# -_V2.net
KiCad netlist of a schematic drawn in EasyEDA Pro
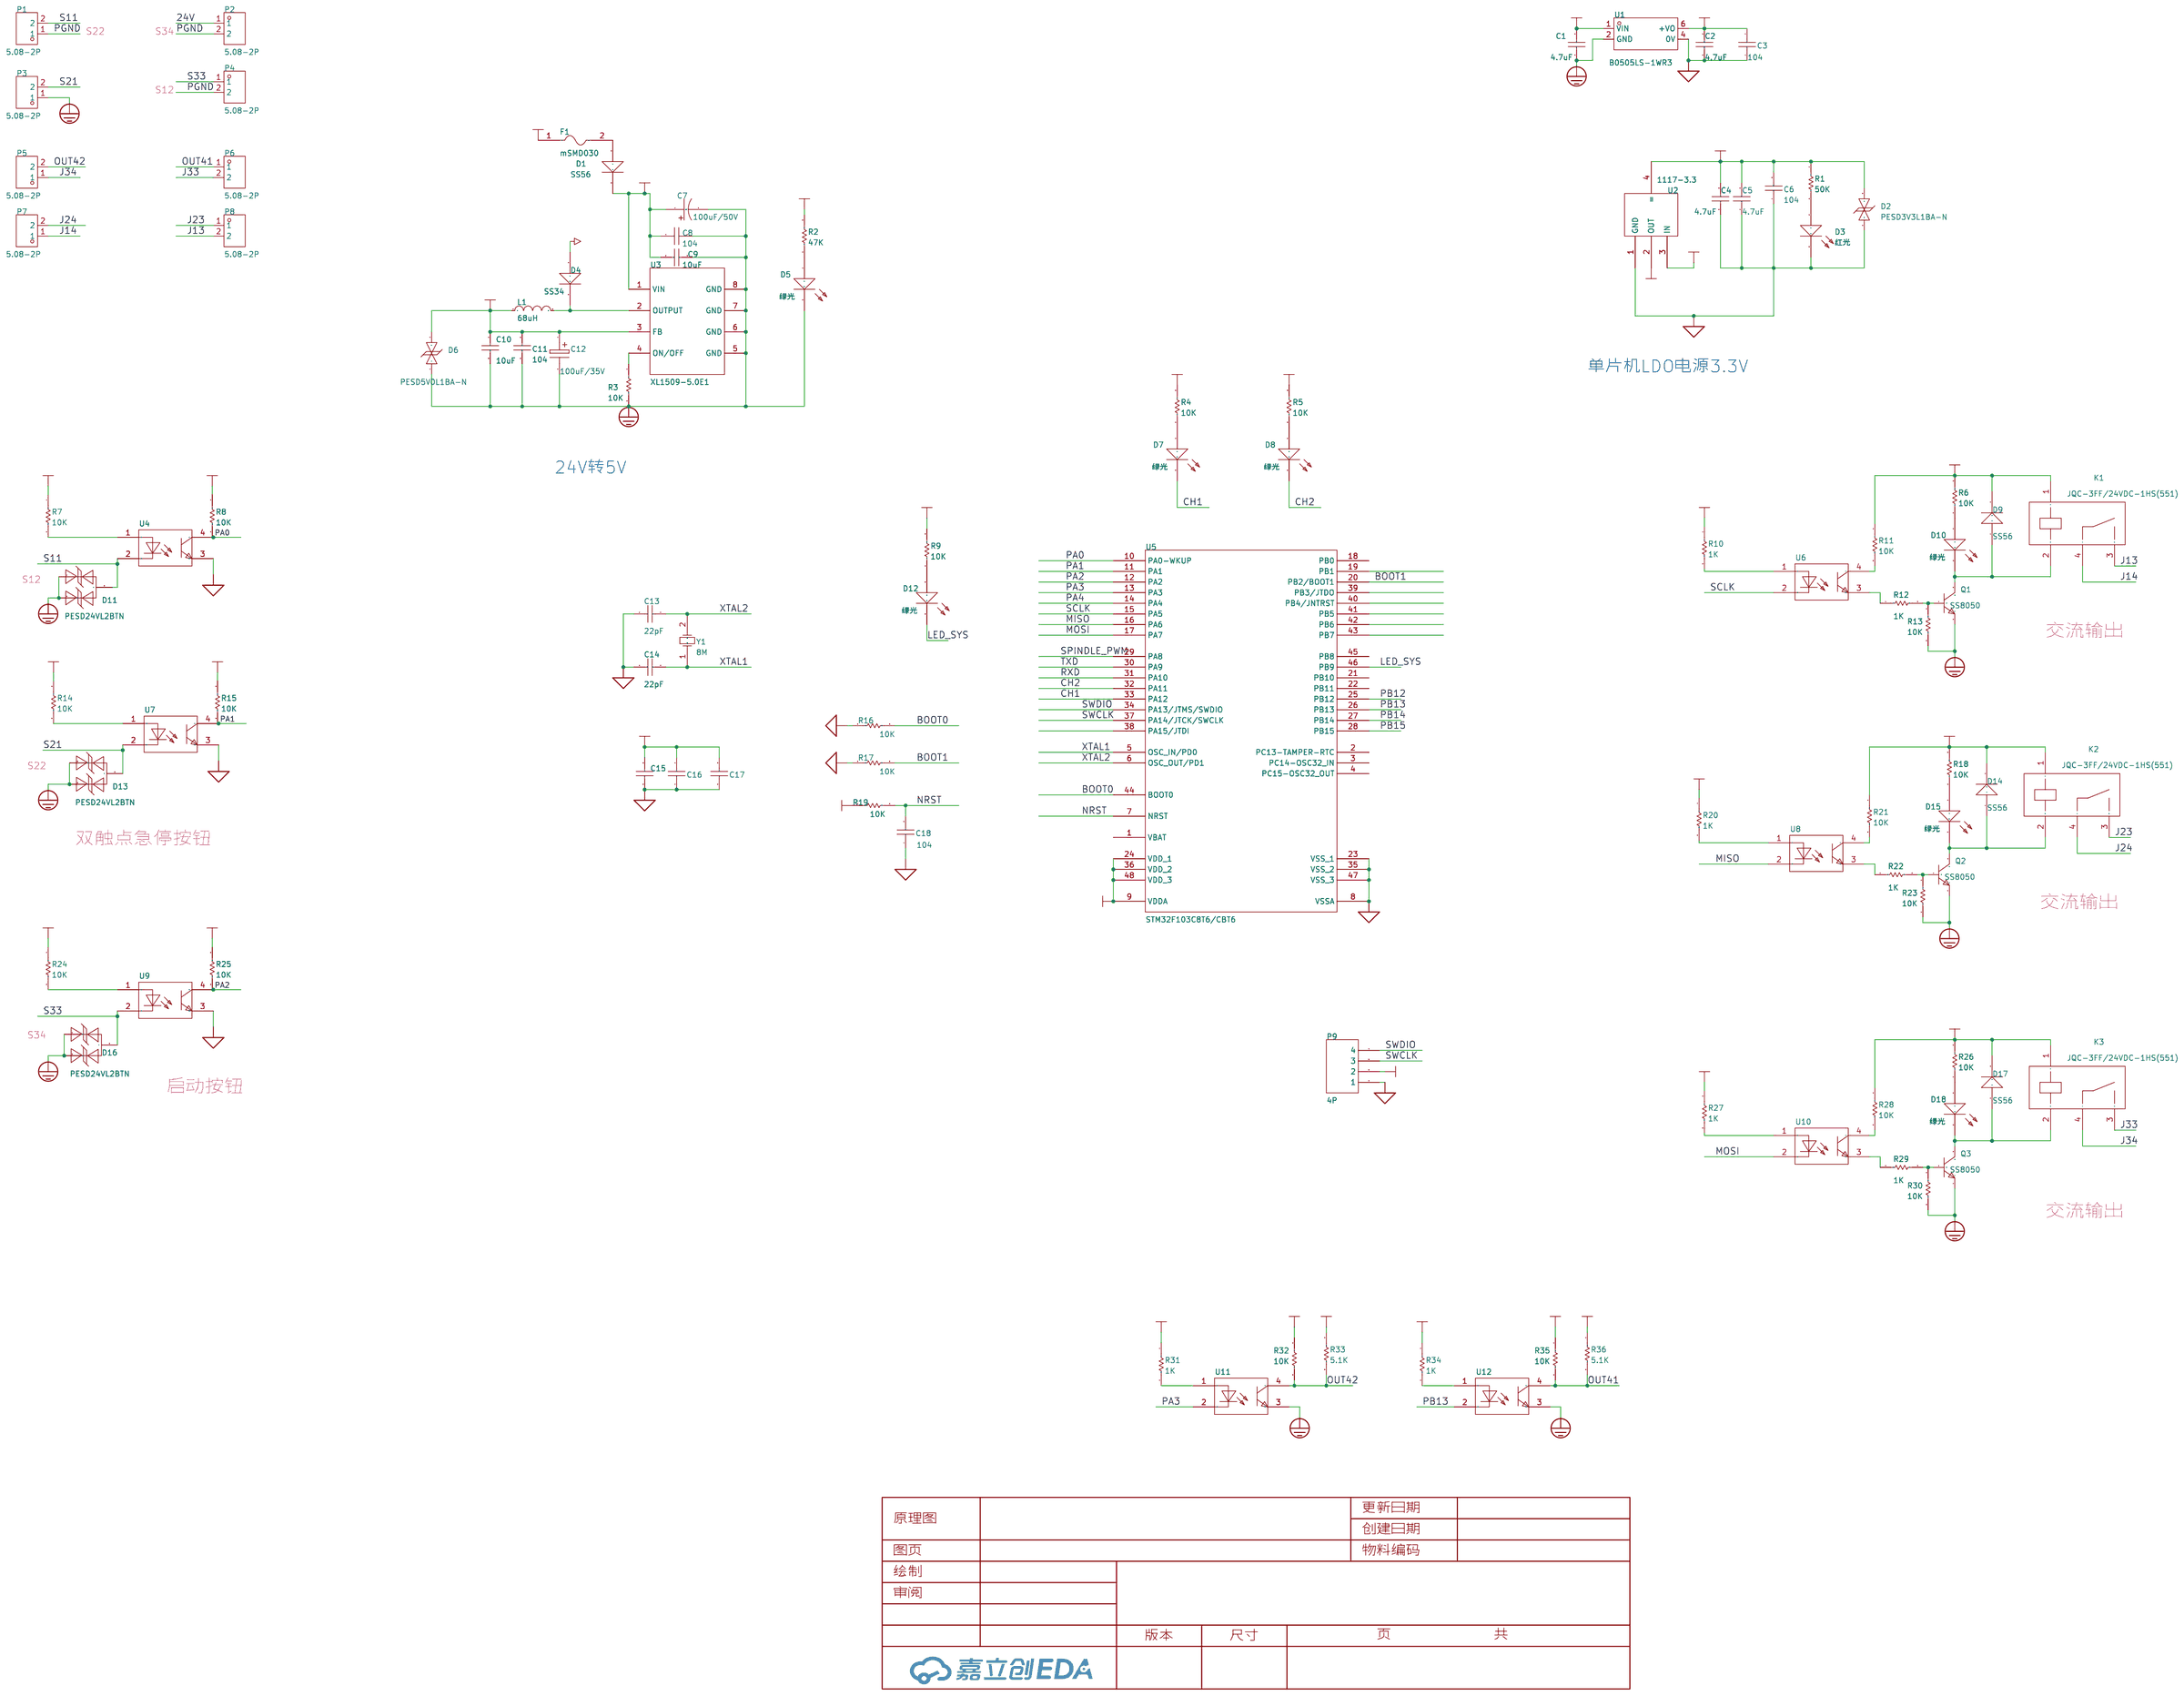
[diagram p0: schematic sheet]

(export (version "E")
  (design (tool "Eeschema 10.0.6"))
  (components
    (comp (ref "C1") (value "4.7uF") (libsource (lib "easyedapro") (part "CAP")))
    (comp (ref "C2") (value "4.7uF") (libsource (lib "easyedapro") (part "CAP")))
    (comp (ref "C3") (value "104") (libsource (lib "easyedapro") (part "CAP")))
    (comp (ref "C4") (value "4.7uF") (libsource (lib "easyedapro") (part "CAP")))
    (comp (ref "C5") (value "4.7uF") (libsource (lib "easyedapro") (part "CAP")))
    (comp (ref "C6")
      (value "104")
      (footprint "easyedapro:0603C")
      (description "Capacitor (Semiconductor SIM Model)")
      (libsource (lib "easyedapro") (part "Cap Semi"))
    )
    (comp (ref "C7")
      (value "100uF/50V")
      (footprint "easyedapro:CAP-SMD_BD10.0-L10.3-W10.3-LS11.0-R-RD")
      (fields (field (name "Manufacturer Part") "VZH101M1HTR-1008") (field (name "Manufacturer") "lelon(立隆)"))
      (libsource (lib "easyedapro") (part "VZH101M1HTR-1008"))
    )
    (comp (ref "C8")
      (value "104")
      (footprint "easyedapro:0603C")
      (description "Capacitor (Semiconductor SIM Model)")
      (libsource (lib "easyedapro") (part "Cap Semi"))
    )
    (comp (ref "C9") (value "10uF") (libsource (lib "easyedapro") (part "CAP")))
    (comp (ref "C10") (value "10uF") (libsource (lib "easyedapro") (part "CAP")))
    (comp (ref "C11")
      (value "104")
      (footprint "easyedapro:0603C")
      (description "Capacitor (Semiconductor SIM Model)")
      (libsource (lib "easyedapro") (part "Cap Semi"))
    )
    (comp (ref "C12")
      (value "100uF/35V")
      (footprint "easyedapro:0603C")
      (libsource (lib "easyedapro") (part "ELECTRO1"))
    )
    (comp (ref "C13")
      (value "100pF")
      (footprint "easyedapro:0603C")
      (description "Capacitor (Semiconductor SIM Model)")
      (libsource (lib "easyedapro") (part "Cap Semi"))
    )
    (comp (ref "C14")
      (value "100pF")
      (footprint "easyedapro:0603C")
      (description "Capacitor (Semiconductor SIM Model)")
      (libsource (lib "easyedapro") (part "Cap Semi"))
    )
    (comp (ref "C15") (value "104") (footprint "easyedapro:电解电容贴片6X6") (libsource (lib "") (part "CAP_1")))
    (comp (ref "C16") (value "104") (footprint "easyedapro:电解电容贴片6X6") (libsource (lib "") (part "CAP_1")))
    (comp (ref "C17") (value "104") (footprint "easyedapro:电解电容贴片6X6") (libsource (lib "") (part "CAP_1")))
    (comp (ref "C18")
      (value "104")
      (footprint "easyedapro:0603C")
      (description "Capacitor (Semiconductor SIM Model)")
      (libsource (lib "easyedapro") (part "Cap Semi"))
    )
    (comp (ref "D1") (value "SS56") (footprint "easyedapro:SMA") (libsource (lib "") (part "1N4148_1")))
    (comp (ref "D2")
      (value "PESD3V3L1BA-N")
      (footprint "easyedapro:SOD-523_L1.2-W0.8-LS1.6-BI")
      (description "极性:Bidirectional;反向关断电压（典型值）:5V (Max);击穿电压（最小值）:6V;箝位电压:15V;峰值脉冲电流（10/1000us）:5A (8/20us);")
      (fields (field (name "Manufacturer") "BORN伯恩半导体"))
      (libsource (lib "easyedapro") (part "PESD5V0S1BBN"))
    )
    (comp (ref "D3")
      (value "红光")
      (footprint "easyedapro:0603LED")
      (libsource (lib "easyedapro") (part "LED"))
    )
    (comp (ref "D4") (value "SS34") (libsource (lib "easyedapro") (part "1N4148")))
    (comp (ref "D5")
      (value "绿光")
      (footprint "easyedapro:0603LED")
      (libsource (lib "easyedapro") (part "LED"))
    )
    (comp (ref "D6")
      (value "PESD5V0L1BA-N")
      (footprint "easyedapro:SOD-523_L1.2-W0.8-LS1.6-BI")
      (description "极性:Bidirectional;反向关断电压（典型值）:5V (Max);击穿电压（最小值）:6V;箝位电压:15V;峰值脉冲电流（10/1000us）:5A (8/20us);")
      (fields (field (name "Manufacturer") "BORN伯恩半导体"))
      (libsource (lib "easyedapro") (part "PESD5V0S1BBN"))
    )
    (comp (ref "D7")
      (value "绿光")
      (footprint "easyedapro:0603LED")
      (libsource (lib "easyedapro") (part "LED"))
    )
    (comp (ref "D8")
      (value "绿光")
      (footprint "easyedapro:0603LED")
      (libsource (lib "easyedapro") (part "LED"))
    )
    (comp (ref "D9") (value "SS56") (footprint "easyedapro:SMA") (libsource (lib "") (part "1N4148_1")))
    (comp (ref "D10")
      (value "绿光")
      (footprint "easyedapro:0603LED")
      (libsource (lib "easyedapro") (part "LED"))
    )
    (comp (ref "D11")
      (value "PESD24VL2BTN")
      (footprint "easyedapro:SOT-23-3_L2.9-W1.6-P1.90-LS2.8-BR")
      (description "极性:Bidirectional;反向关断电压（典型值）:24V (Max);击穿电压（最小值）:26.7V;箝位电压:48V;峰值脉冲电流（10/1000us）:6A (8/20us);")
      (fields (field (name "Manufacturer") "BORN伯恩半导体"))
      (libsource (lib "easyedapro") (part "PESD24VL2BTN"))
    )
    (comp (ref "D12")
      (value "绿光")
      (footprint "easyedapro:0603LED")
      (libsource (lib "easyedapro") (part "LED"))
    )
    (comp (ref "D13")
      (value "PESD24VL2BTN")
      (footprint "easyedapro:SOT-23-3_L2.9-W1.6-P1.90-LS2.8-BR")
      (description "极性:Bidirectional;反向关断电压（典型值）:24V (Max);击穿电压（最小值）:26.7V;箝位电压:48V;峰值脉冲电流（10/1000us）:6A (8/20us);")
      (fields (field (name "Manufacturer") "BORN伯恩半导体"))
      (libsource (lib "easyedapro") (part "PESD24VL2BTN"))
    )
    (comp (ref "D14") (value "SS56") (footprint "easyedapro:SMA") (libsource (lib "") (part "1N4148_1")))
    (comp (ref "D15")
      (value "绿光")
      (footprint "easyedapro:0603LED")
      (libsource (lib "easyedapro") (part "LED"))
    )
    (comp (ref "D16")
      (value "PESD24VL2BTN")
      (footprint "easyedapro:SOT-23-3_L2.9-W1.6-P1.90-LS2.8-BR")
      (description "极性:Bidirectional;反向关断电压（典型值）:24V (Max);击穿电压（最小值）:26.7V;箝位电压:48V;峰值脉冲电流（10/1000us）:6A (8/20us);")
      (fields (field (name "Manufacturer") "BORN伯恩半导体"))
      (libsource (lib "easyedapro") (part "PESD24VL2BTN"))
    )
    (comp (ref "D17") (value "SS56") (footprint "easyedapro:SMA") (libsource (lib "") (part "1N4148_1")))
    (comp (ref "D18")
      (value "绿光")
      (footprint "easyedapro:0603LED")
      (libsource (lib "easyedapro") (part "LED"))
    )
    (comp (ref "F1")
      (value "mSMD030")
      (footprint "easyedapro:F1812")
      (description "最大电压:30V;最大电流:100A;保持电流:300mA;跳闸电流:600mA;")
      (fields (field (name "Manufacturer") "台湾陆海"))
      (libsource (lib "easyedapro") (part "mSMD030"))
    )
    (comp (ref "K1")
      (value "JQC-3FF/24VDC-1HS(551)")
      (footprint "easyedapro:RELAY-TH_JQC-3FF-1HXX")
      (description "继电器类型:General Purpose;线圈类型:Non Latching;线圈电压:24VDC;触点形式:SPST-NO;触点的额定电流:15A;")
      (fields (field (name "Manufacturer") "HF(宏发)"))
      (libsource (lib "easyedapro") (part "JQC-3FF/024-1HS"))
    )
    (comp (ref "K2")
      (value "JQC-3FF/24VDC-1HS(551)")
      (footprint "easyedapro:RELAY-TH_JQC-3FF-1HXX")
      (description "继电器类型:General Purpose;线圈类型:Non Latching;线圈电压:24VDC;触点形式:SPST-NO;触点的额定电流:15A;")
      (fields (field (name "Manufacturer") "HF(宏发)"))
      (libsource (lib "easyedapro") (part "JQC-3FF/024-1HS"))
    )
    (comp (ref "K3")
      (value "JQC-3FF/24VDC-1HS(551)")
      (footprint "easyedapro:RELAY-TH_JQC-3FF-1HXX")
      (description "继电器类型:General Purpose;线圈类型:Non Latching;线圈电压:24VDC;触点形式:SPST-NO;触点的额定电流:15A;")
      (fields (field (name "Manufacturer") "HF(宏发)"))
      (libsource (lib "easyedapro") (part "JQC-3FF/024-1HS"))
    )
    (comp (ref "L1")
      (value "68uH")
      (footprint "easyedapro:IND-SMD_L7.0-W7.0_SMDRI74-330MT")
      (description "电感值:33uH;精度:±20%;额定电流:960mA;饱和电流(Isat):1.8A;类型:屏蔽电感;")
      (fields (field (name "Manufacturer Part") "SMDRI74-330MT") (field (name "Manufacturer") "SXN(顺翔诺)"))
      (libsource (lib "easyedapro") (part "SMDRI74-330MT"))
    )
    (comp (ref "P1")
      (value "5.08-2P")
      (footprint "easyedapro:CONN-TH_2P-P5.08_DB128L-5.08-2P")
      (fields (field (name "Manufacturer") "DIBO(地博电气)"))
      (libsource (lib "easyedapro") (part "DB128L-5.08-2P"))
    )
    (comp (ref "P2")
      (value "5.08-2P")
      (footprint "easyedapro:CONN-TH_2P-P5.08_DB128L-5.08-2P")
      (fields (field (name "Manufacturer") "DIBO(地博电气)"))
      (libsource (lib "easyedapro") (part "DB128L-5.08-2P"))
    )
    (comp (ref "P3")
      (value "5.08-2P")
      (footprint "easyedapro:CONN-TH_2P-P5.08_DB128L-5.08-2P")
      (fields (field (name "Manufacturer") "DIBO(地博电气)"))
      (libsource (lib "easyedapro") (part "DB128L-5.08-2P"))
    )
    (comp (ref "P4")
      (value "5.08-2P")
      (footprint "easyedapro:CONN-TH_2P-P5.08_DB128L-5.08-2P")
      (fields (field (name "Manufacturer") "DIBO(地博电气)"))
      (libsource (lib "easyedapro") (part "DB128L-5.08-2P"))
    )
    (comp (ref "P5")
      (value "5.08-2P")
      (footprint "easyedapro:CONN-TH_2P-P5.08_DB128L-5.08-2P")
      (fields (field (name "Manufacturer") "DIBO(地博电气)"))
      (libsource (lib "easyedapro") (part "DB128L-5.08-2P"))
    )
    (comp (ref "P6")
      (value "5.08-2P")
      (footprint "easyedapro:CONN-TH_2P-P5.08_DB128L-5.08-2P")
      (fields (field (name "Manufacturer") "DIBO(地博电气)"))
      (libsource (lib "easyedapro") (part "DB128L-5.08-2P"))
    )
    (comp (ref "P7")
      (value "5.08-2P")
      (footprint "easyedapro:CONN-TH_2P-P5.08_DB128L-5.08-2P")
      (fields (field (name "Manufacturer") "DIBO(地博电气)"))
      (libsource (lib "easyedapro") (part "DB128L-5.08-2P"))
    )
    (comp (ref "P8")
      (value "5.08-2P")
      (footprint "easyedapro:CONN-TH_2P-P5.08_DB128L-5.08-2P")
      (fields (field (name "Manufacturer") "DIBO(地博电气)"))
      (libsource (lib "easyedapro") (part "DB128L-5.08-2P"))
    )
    (comp (ref "P9") (value "4P") (libsource (lib "easyedapro") (part "4P")))
    (comp (ref "Q1")
      (value "SS8050")
      (footprint "easyedapro:SOT-23-3_L2.9-W1.3-P1.90-LS2.4-BR")
      (fields (field (name "Manufacturer") "CJ（江苏长电/长晶）"))
      (libsource (lib "easyedapro") (part "SS8050_C2150"))
    )
    (comp (ref "Q2")
      (value "SS8050")
      (footprint "easyedapro:SOT-23-3_L2.9-W1.3-P1.90-LS2.4-BR")
      (fields (field (name "Manufacturer") "CJ（江苏长电/长晶）"))
      (libsource (lib "easyedapro") (part "SS8050_C2150"))
    )
    (comp (ref "Q3")
      (value "SS8050")
      (footprint "easyedapro:SOT-23-3_L2.9-W1.3-P1.90-LS2.4-BR")
      (fields (field (name "Manufacturer") "CJ（江苏长电/长晶）"))
      (libsource (lib "easyedapro") (part "SS8050_C2150"))
    )
    (comp (ref "R1")
      (value "50K")
      (footprint "easyedapro:0603R")
      (description "Resistor")
      (libsource (lib "easyedapro") (part "RES"))
    )
    (comp (ref "R2")
      (value "47K")
      (footprint "easyedapro:0603R")
      (description "Resistor")
      (libsource (lib "easyedapro") (part "RES"))
    )
    (comp (ref "R3")
      (value "10K")
      (footprint "easyedapro:0603R")
      (description "Resistor")
      (libsource (lib "easyedapro") (part "RES"))
    )
    (comp (ref "R4")
      (value "10K")
      (footprint "easyedapro:0603R")
      (description "Resistor")
      (libsource (lib "easyedapro") (part "RES"))
    )
    (comp (ref "R5")
      (value "10K")
      (footprint "easyedapro:0603R")
      (description "Resistor")
      (libsource (lib "easyedapro") (part "RES"))
    )
    (comp (ref "R6")
      (value "10K")
      (footprint "easyedapro:0603R")
      (description "Resistor")
      (libsource (lib "easyedapro") (part "RES"))
    )
    (comp (ref "R7")
      (value "10K")
      (footprint "easyedapro:0603R")
      (description "Resistor")
      (libsource (lib "easyedapro") (part "RES"))
    )
    (comp (ref "R8")
      (value "10K")
      (footprint "easyedapro:0603R")
      (description "Resistor")
      (libsource (lib "easyedapro") (part "RES"))
    )
    (comp (ref "R9")
      (value "10K")
      (footprint "easyedapro:0603R")
      (description "Resistor")
      (libsource (lib "easyedapro") (part "RES"))
    )
    (comp (ref "R10")
      (value "1K")
      (footprint "easyedapro:0603R")
      (description "Resistor")
      (libsource (lib "easyedapro") (part "RES"))
    )
    (comp (ref "R11")
      (value "10K")
      (footprint "easyedapro:0603R")
      (description "Resistor")
      (libsource (lib "easyedapro") (part "RES"))
    )
    (comp (ref "R12")
      (value "1K")
      (footprint "easyedapro:0603R")
      (description "Resistor")
      (libsource (lib "easyedapro") (part "RES"))
    )
    (comp (ref "R13")
      (value "10K")
      (footprint "easyedapro:0603R")
      (description "Resistor")
      (libsource (lib "easyedapro") (part "RES"))
    )
    (comp (ref "R14")
      (value "10K")
      (footprint "easyedapro:0603R")
      (description "Resistor")
      (libsource (lib "easyedapro") (part "RES"))
    )
    (comp (ref "R15")
      (value "10K")
      (footprint "easyedapro:0603R")
      (description "Resistor")
      (libsource (lib "easyedapro") (part "RES"))
    )
    (comp (ref "R16")
      (value "10K")
      (footprint "easyedapro:0603R")
      (description "Resistor")
      (libsource (lib "easyedapro") (part "RES"))
    )
    (comp (ref "R17")
      (value "10K")
      (footprint "easyedapro:0603R")
      (description "Resistor")
      (libsource (lib "easyedapro") (part "RES"))
    )
    (comp (ref "R18")
      (value "10K")
      (footprint "easyedapro:0603R")
      (description "Resistor")
      (libsource (lib "easyedapro") (part "RES"))
    )
    (comp (ref "R19")
      (value "10K")
      (footprint "easyedapro:0603R")
      (description "Resistor")
      (libsource (lib "easyedapro") (part "RES"))
    )
    (comp (ref "R20")
      (value "1K")
      (footprint "easyedapro:0603R")
      (description "Resistor")
      (libsource (lib "easyedapro") (part "RES"))
    )
    (comp (ref "R21")
      (value "10K")
      (footprint "easyedapro:0603R")
      (description "Resistor")
      (libsource (lib "easyedapro") (part "RES"))
    )
    (comp (ref "R22")
      (value "1K")
      (footprint "easyedapro:0603R")
      (description "Resistor")
      (libsource (lib "easyedapro") (part "RES"))
    )
    (comp (ref "R23")
      (value "10K")
      (footprint "easyedapro:0603R")
      (description "Resistor")
      (libsource (lib "easyedapro") (part "RES"))
    )
    (comp (ref "R24")
      (value "10K")
      (footprint "easyedapro:0603R")
      (description "Resistor")
      (libsource (lib "easyedapro") (part "RES"))
    )
    (comp (ref "R25")
      (value "10K")
      (footprint "easyedapro:0603R")
      (description "Resistor")
      (libsource (lib "easyedapro") (part "RES"))
    )
    (comp (ref "R26")
      (value "10K")
      (footprint "easyedapro:0603R")
      (description "Resistor")
      (libsource (lib "easyedapro") (part "RES"))
    )
    (comp (ref "R27")
      (value "1K")
      (footprint "easyedapro:0603R")
      (description "Resistor")
      (libsource (lib "easyedapro") (part "RES"))
    )
    (comp (ref "R28")
      (value "10K")
      (footprint "easyedapro:0603R")
      (description "Resistor")
      (libsource (lib "easyedapro") (part "RES"))
    )
    (comp (ref "R29")
      (value "1K")
      (footprint "easyedapro:0603R")
      (description "Resistor")
      (libsource (lib "easyedapro") (part "RES"))
    )
    (comp (ref "R30")
      (value "10K")
      (footprint "easyedapro:0603R")
      (description "Resistor")
      (libsource (lib "easyedapro") (part "RES"))
    )
    (comp (ref "R31")
      (value "1K")
      (footprint "easyedapro:0603R")
      (description "Resistor")
      (libsource (lib "easyedapro") (part "RES"))
    )
    (comp (ref "R32")
      (value "10K")
      (footprint "easyedapro:0603R")
      (description "Resistor")
      (libsource (lib "easyedapro") (part "RES"))
    )
    (comp (ref "R33")
      (value "10K")
      (footprint "easyedapro:0603R")
      (description "Resistor")
      (libsource (lib "easyedapro") (part "RES"))
    )
    (comp (ref "R34")
      (value "1K")
      (footprint "easyedapro:0603R")
      (description "Resistor")
      (libsource (lib "easyedapro") (part "RES"))
    )
    (comp (ref "R35")
      (value "10K")
      (footprint "easyedapro:0603R")
      (description "Resistor")
      (libsource (lib "easyedapro") (part "RES"))
    )
    (comp (ref "R36")
      (value "10K")
      (footprint "easyedapro:0603R")
      (description "Resistor")
      (libsource (lib "easyedapro") (part "RES"))
    )
    (comp (ref "U1")
      (value "B0505LS-1WR3")
      (footprint "easyedapro:PWRM-TH_BXXXXLS-1WR3")
      (description "100%国产化器件，高可靠性，具备ROHS、REACH、CE认证产品")
      (fields (field (name "Manufacturer") "DEXU(德旭电子)"))
      (libsource (lib "easyedapro") (part "B0505LS-1WR3_C909800"))
    )
    (comp (ref "U2")
      (value "1117-3.3")
      (footprint "easyedapro:SOT-223")
      (libsource (lib "easyedapro") (part "LM1117"))
    )
    (comp (ref "U3")
      (value "XL1509-5.0E1")
      (footprint "easyedapro:SOIC-8_L5.0-W4.0-P1.27-LS6.0-BL")
      (description "功能类型:降压型;同步整流:-;输出通道数:-;拓扑结构:-;输入电压:-;输出电流(最大值):-;开关频率:-;")
      (fields (field (name "Manufacturer") "XLSEMI(芯龙)"))
      (libsource (lib "easyedapro") (part "XL1509-5.0E1"))
    )
    (comp (ref "U4")
      (value "LTV-357T-C")
      (footprint "easyedapro:SOP-4_L4.4-W3.9-P2.54-LS7.0-TL")
      (fields (field (name "Manufacturer") "LITEON(光宝)"))
      (libsource (lib "easyedapro") (part "LTV-357T-C"))
    )
    (comp (ref "U5")
      (value "STM32F103C8T6/CBT6")
      (footprint "easyedapro:LQFP48")
      (description "STM32 ARM-based 32-bit MCU with 32 Kbytes Flash, 48-pin LQFP, Industrial Temperature")
      (libsource (lib "easyedapro") (part "STM32F103C6T6"))
    )
    (comp (ref "U6")
      (value "LTV-357T-C")
      (footprint "easyedapro:SOP-4_L4.4-W3.9-P2.54-LS7.0-TL")
      (fields (field (name "Manufacturer") "LITEON(光宝)"))
      (libsource (lib "easyedapro") (part "LTV-357T-C"))
    )
    (comp (ref "U7")
      (value "LTV-357T-C")
      (footprint "easyedapro:SOP-4_L4.4-W3.9-P2.54-LS7.0-TL")
      (fields (field (name "Manufacturer") "LITEON(光宝)"))
      (libsource (lib "easyedapro") (part "LTV-357T-C"))
    )
    (comp (ref "U8")
      (value "LTV-357T-C")
      (footprint "easyedapro:SOP-4_L4.4-W3.9-P2.54-LS7.0-TL")
      (fields (field (name "Manufacturer") "LITEON(光宝)"))
      (libsource (lib "easyedapro") (part "LTV-357T-C"))
    )
    (comp (ref "U9")
      (value "LTV-357T-C")
      (footprint "easyedapro:SOP-4_L4.4-W3.9-P2.54-LS7.0-TL")
      (fields (field (name "Manufacturer") "LITEON(光宝)"))
      (libsource (lib "easyedapro") (part "LTV-357T-C"))
    )
    (comp (ref "U10")
      (value "LTV-357T-C")
      (footprint "easyedapro:SOP-4_L4.4-W3.9-P2.54-LS7.0-TL")
      (fields (field (name "Manufacturer") "LITEON(光宝)"))
      (libsource (lib "easyedapro") (part "LTV-357T-C"))
    )
    (comp (ref "U11")
      (value "LTV-357T-C")
      (footprint "easyedapro:SOP-4_L4.4-W3.9-P2.54-LS7.0-TL")
      (fields (field (name "Manufacturer") "LITEON(光宝)"))
      (libsource (lib "easyedapro") (part "LTV-357T-C"))
    )
    (comp (ref "U12")
      (value "LTV-357T-C")
      (footprint "easyedapro:SOP-4_L4.4-W3.9-P2.54-LS7.0-TL")
      (fields (field (name "Manufacturer") "LITEON(光宝)"))
      (libsource (lib "easyedapro") (part "LTV-357T-C"))
    )
    (comp (ref "Y1")
      (value "8M")
      (footprint "easyedapro:晶振贴片49SSMD")
      (description "Crystal Oscillator")
      (libsource (lib "easyedapro") (part "XTAL"))
    )
  )
  (nets
    (net (code "1") (name "/BOOT0") (class "Default")
      (node (ref "R16") (pin "2") (pinfunction "2_2") (pintype "unspecified"))
      (node (ref "U5") (pin "44") (pinfunction "BOOT0_44") (pintype "input"))
    )
    (net (code "2") (name "/BOOT1") (class "Default")
      (node (ref "R17") (pin "2") (pinfunction "2_2") (pintype "unspecified"))
      (node (ref "U5") (pin "20") (pinfunction "PB2/BOOT1_20") (pintype "bidirectional"))
    )
    (net (code "3") (name "/CH1") (class "Default")
      (node (ref "D7") (pin "2") (pinfunction "2_2") (pintype "unspecified"))
      (node (ref "U5") (pin "33") (pinfunction "PA12_33") (pintype "bidirectional"))
    )
    (net (code "4") (name "/CH2") (class "Default")
      (node (ref "D8") (pin "2") (pinfunction "2_2") (pintype "unspecified"))
      (node (ref "U5") (pin "32") (pinfunction "PA11_32") (pintype "bidirectional"))
    )
    (net (code "5") (name "/J13") (class "Default")
      (node (ref "K1") (pin "3") (pinfunction "3_3") (pintype "input"))
      (node (ref "P8") (pin "2") (pinfunction "2_2") (pintype "input"))
    )
    (net (code "6") (name "/J14") (class "Default")
      (node (ref "K1") (pin "4") (pinfunction "4_4") (pintype "input"))
      (node (ref "P7") (pin "1") (pinfunction "1_1") (pintype "input"))
    )
    (net (code "7") (name "/J23") (class "Default")
      (node (ref "K2") (pin "3") (pinfunction "3_3") (pintype "input"))
      (node (ref "P8") (pin "1") (pinfunction "1_1") (pintype "input"))
    )
    (net (code "8") (name "/J24") (class "Default")
      (node (ref "K2") (pin "4") (pinfunction "4_4") (pintype "input"))
      (node (ref "P7") (pin "2") (pinfunction "2_2") (pintype "input"))
    )
    (net (code "9") (name "/J33") (class "Default")
      (node (ref "K3") (pin "3") (pinfunction "3_3") (pintype "input"))
      (node (ref "P6") (pin "2") (pinfunction "2_2") (pintype "input"))
    )
    (net (code "10") (name "/J34") (class "Default")
      (node (ref "K3") (pin "4") (pinfunction "4_4") (pintype "input"))
      (node (ref "P5") (pin "1") (pinfunction "1_1") (pintype "input"))
    )
    (net (code "11") (name "/LED_SYS") (class "Default")
      (node (ref "D12") (pin "2") (pinfunction "2_2") (pintype "unspecified"))
      (node (ref "U5") (pin "46") (pinfunction "PB9_46") (pintype "bidirectional"))
    )
    (net (code "12") (name "/MISO") (class "Default")
      (node (ref "U5") (pin "16") (pinfunction "PA6_16") (pintype "bidirectional"))
      (node (ref "U8") (pin "2") (pinfunction "2_2") (pintype "unspecified"))
    )
    (net (code "13") (name "/MOSI") (class "Default")
      (node (ref "U10") (pin "2") (pinfunction "2_2") (pintype "unspecified"))
      (node (ref "U5") (pin "17") (pinfunction "PA7_17") (pintype "bidirectional"))
    )
    (net (code "14") (name "/NRST") (class "Default")
      (node (ref "C18") (pin "2") (pinfunction "2_2") (pintype "unspecified"))
      (node (ref "R19") (pin "2") (pinfunction "2_2") (pintype "unspecified"))
      (node (ref "U5") (pin "7") (pinfunction "NRST_7") (pintype "bidirectional"))
    )
    (net (code "15") (name "/OUT41") (class "Default")
      (node (ref "P6") (pin "1") (pinfunction "1_1") (pintype "input"))
      (node (ref "R35") (pin "2") (pinfunction "2_2") (pintype "unspecified"))
      (node (ref "R36") (pin "2") (pinfunction "2_2") (pintype "unspecified"))
      (node (ref "U12") (pin "4") (pinfunction "4_4") (pintype "unspecified"))
    )
    (net (code "16") (name "/OUT42") (class "Default")
      (node (ref "P5") (pin "2") (pinfunction "2_2") (pintype "input"))
      (node (ref "R32") (pin "2") (pinfunction "2_2") (pintype "unspecified"))
      (node (ref "R33") (pin "2") (pinfunction "2_2") (pintype "unspecified"))
      (node (ref "U11") (pin "4") (pinfunction "4_4") (pintype "unspecified"))
    )
    (net (code "17") (name "/PA0") (class "Default")
      (node (ref "R8") (pin "2") (pinfunction "2_2") (pintype "unspecified"))
      (node (ref "U4") (pin "4") (pinfunction "4_4") (pintype "unspecified"))
      (node (ref "U5") (pin "10") (pinfunction "PA0-WKUP_10") (pintype "bidirectional"))
    )
    (net (code "18") (name "/PA1") (class "Default")
      (node (ref "R15") (pin "2") (pinfunction "2_2") (pintype "unspecified"))
      (node (ref "U5") (pin "11") (pinfunction "PA1_11") (pintype "bidirectional"))
      (node (ref "U7") (pin "4") (pinfunction "4_4") (pintype "unspecified"))
    )
    (net (code "19") (name "/PA2") (class "Default")
      (node (ref "R25") (pin "2") (pinfunction "2_2") (pintype "unspecified"))
      (node (ref "U5") (pin "12") (pinfunction "PA2_12") (pintype "bidirectional"))
      (node (ref "U9") (pin "4") (pinfunction "4_4") (pintype "unspecified"))
    )
    (net (code "20") (name "/PA3") (class "Default")
      (node (ref "U11") (pin "2") (pinfunction "2_2") (pintype "unspecified"))
      (node (ref "U5") (pin "13") (pinfunction "PA3_13") (pintype "bidirectional"))
    )
    (net (code "21") (name "/PA4") (class "Default")
      (node (ref "U5") (pin "14") (pinfunction "PA4_14") (pintype "bidirectional"))
    )
    (net (code "22") (name "/PB12") (class "Default")
      (node (ref "U5") (pin "25") (pinfunction "PB12_25") (pintype "bidirectional"))
    )
    (net (code "23") (name "/PB13") (class "Default")
      (node (ref "U12") (pin "2") (pinfunction "2_2") (pintype "unspecified"))
      (node (ref "U5") (pin "26") (pinfunction "PB13_26") (pintype "bidirectional"))
    )
    (net (code "24") (name "/PB14") (class "Default")
      (node (ref "U5") (pin "27") (pinfunction "PB14_27") (pintype "bidirectional"))
    )
    (net (code "25") (name "/PB15") (class "Default")
      (node (ref "U5") (pin "28") (pinfunction "PB15_28") (pintype "bidirectional"))
    )
    (net (code "26") (name "/RXD") (class "Default")
      (node (ref "U5") (pin "31") (pinfunction "PA10_31") (pintype "bidirectional"))
    )
    (net (code "27") (name "/S11") (class "Default")
      (node (ref "D11") (pin "3") (pinfunction "A_3") (pintype "input"))
      (node (ref "P1") (pin "2") (pinfunction "2_2") (pintype "input"))
      (node (ref "U4") (pin "2") (pinfunction "2_2") (pintype "unspecified"))
    )
    (net (code "28") (name "/S21") (class "Default")
      (node (ref "D13") (pin "3") (pinfunction "A_3") (pintype "input"))
      (node (ref "P3") (pin "2") (pinfunction "2_2") (pintype "input"))
      (node (ref "U7") (pin "2") (pinfunction "2_2") (pintype "unspecified"))
    )
    (net (code "29") (name "/S33") (class "Default")
      (node (ref "D16") (pin "3") (pinfunction "A_3") (pintype "input"))
      (node (ref "P4") (pin "1") (pinfunction "1_1") (pintype "input"))
      (node (ref "U9") (pin "2") (pinfunction "2_2") (pintype "unspecified"))
    )
    (net (code "30") (name "/SCLK") (class "Default")
      (node (ref "U5") (pin "15") (pinfunction "PA5_15") (pintype "bidirectional"))
      (node (ref "U6") (pin "2") (pinfunction "2_2") (pintype "unspecified"))
    )
    (net (code "31") (name "/SPINDLE_PWM") (class "Default")
      (node (ref "U5") (pin "29") (pinfunction "PA8_29") (pintype "bidirectional"))
    )
    (net (code "32") (name "/SWCLK") (class "Default")
      (node (ref "P9") (pin "3") (pinfunction "3_3") (pintype "input"))
      (node (ref "U5") (pin "37") (pinfunction "PA14/JTCK/SWCLK_37") (pintype "bidirectional"))
    )
    (net (code "33") (name "/SWDIO") (class "Default")
      (node (ref "P9") (pin "4") (pinfunction "4_4") (pintype "input"))
      (node (ref "U5") (pin "34") (pinfunction "PA13/JTMS/SWDIO_34") (pintype "bidirectional"))
    )
    (net (code "34") (name "/TXD") (class "Default")
      (node (ref "U5") (pin "30") (pinfunction "PA9_30") (pintype "bidirectional"))
    )
    (net (code "35") (name "/XTAL1") (class "Default")
      (node (ref "C14") (pin "1") (pinfunction "1_1") (pintype "unspecified"))
      (node (ref "U5") (pin "5") (pinfunction "OSC_IN/PD0_5") (pintype "input"))
      (node (ref "Y1") (pin "1") (pinfunction "OSC1_1") (pintype "unspecified"))
    )
    (net (code "36") (name "/XTAL2") (class "Default")
      (node (ref "C13") (pin "1") (pinfunction "1_1") (pintype "unspecified"))
      (node (ref "U5") (pin "6") (pinfunction "OSC_OUT/PD1_6") (pintype "output"))
      (node (ref "Y1") (pin "2") (pinfunction "OSC2_2") (pintype "unspecified"))
    )
    (net (code "37") (name "3V3") (class "Default")
      (node (ref "C15") (pin "2") (pinfunction "2_2") (pintype "unspecified"))
      (node (ref "C16") (pin "2") (pinfunction "2_2") (pintype "unspecified"))
      (node (ref "C17") (pin "2") (pinfunction "2_2") (pintype "unspecified"))
      (node (ref "C4") (pin "2") (pinfunction "2_2") (pintype "input"))
      (node (ref "C5") (pin "2") (pinfunction "2_2") (pintype "input"))
      (node (ref "C6") (pin "2") (pinfunction "2_2") (pintype "unspecified"))
      (node (ref "D2") (pin "2") (pinfunction "2_2") (pintype "input"))
      (node (ref "P9") (pin "2") (pinfunction "2_2") (pintype "input"))
      (node (ref "R1") (pin "1") (pinfunction "1_1") (pintype "unspecified"))
      (node (ref "R10") (pin "1") (pinfunction "1_1") (pintype "unspecified"))
      (node (ref "R15") (pin "1") (pinfunction "1_1") (pintype "unspecified"))
      (node (ref "R19") (pin "1") (pinfunction "1_1") (pintype "unspecified"))
      (node (ref "R20") (pin "1") (pinfunction "1_1") (pintype "unspecified"))
      (node (ref "R25") (pin "1") (pinfunction "1_1") (pintype "unspecified"))
      (node (ref "R27") (pin "1") (pinfunction "1_1") (pintype "unspecified"))
      (node (ref "R31") (pin "1") (pinfunction "1_1") (pintype "unspecified"))
      (node (ref "R34") (pin "1") (pinfunction "1_1") (pintype "unspecified"))
      (node (ref "R4") (pin "2") (pinfunction "2_2") (pintype "unspecified"))
      (node (ref "R5") (pin "2") (pinfunction "2_2") (pintype "unspecified"))
      (node (ref "R8") (pin "1") (pinfunction "1_1") (pintype "unspecified"))
      (node (ref "R9") (pin "2") (pinfunction "2_2") (pintype "unspecified"))
      (node (ref "U2") (pin "2") (pinfunction "OUT_2") (pintype "unspecified"))
      (node (ref "U2") (pin "4") (pinfunction "=_4") (pintype "unspecified"))
      (node (ref "U5") (pin "24") (pinfunction "VDD_1_24") (pintype "unspecified"))
      (node (ref "U5") (pin "36") (pinfunction "VDD_2_36") (pintype "unspecified"))
      (node (ref "U5") (pin "48") (pinfunction "VDD_3_48") (pintype "unspecified"))
      (node (ref "U5") (pin "9") (pinfunction "VDDA_9") (pintype "unspecified"))
    )
    (net (code "38") (name "5V_MCU") (class "Default")
      (node (ref "C2") (pin "2") (pinfunction "2_2") (pintype "input"))
      (node (ref "C3") (pin "2") (pinfunction "2_2") (pintype "input"))
      (node (ref "U1") (pin "6") (pinfunction "+VO_6") (pintype "unspecified"))
      (node (ref "U2") (pin "3") (pinfunction "IN_3") (pintype "unspecified"))
    )
    (net (code "39") (name "5V_VCC") (class "Default")
      (node (ref "C1") (pin "2") (pinfunction "2_2") (pintype "input"))
      (node (ref "C10") (pin "1") (pinfunction "1_1") (pintype "input"))
      (node (ref "C11") (pin "2") (pinfunction "2_2") (pintype "unspecified"))
      (node (ref "C12") (pin "1") (pintype "unspecified"))
      (node (ref "D6") (pin "2") (pinfunction "2_2") (pintype "input"))
      (node (ref "L1") (pin "1") (pinfunction "1_1") (pintype "unspecified"))
      (node (ref "R33") (pin "1") (pinfunction "1_1") (pintype "unspecified"))
      (node (ref "R36") (pin "1") (pinfunction "1_1") (pintype "unspecified"))
      (node (ref "U1") (pin "1") (pinfunction "VIN_1") (pintype "unspecified"))
      (node (ref "U3") (pin "3") (pinfunction "FB_3") (pintype "input"))
    )
    (net (code "40") (name "24V") (class "Default")
      (node (ref "F1") (pin "1") (pinfunction "1_1") (pintype "input"))
      (node (ref "P2") (pin "1") (pinfunction "1_1") (pintype "input"))
    )
    (net (code "41") (name "GND") (class "Default")
      (node (ref "D4") (pin "1") (pinfunction "1_1") (pintype "input"))
    )
    (net (code "42") (name "Net-(D1-Pad1)") (class "Default")
      (node (ref "D1") (pin "1") (pinfunction "1_1") (pintype "unspecified"))
      (node (ref "F1") (pin "2") (pinfunction "2_2") (pintype "input"))
    )
    (net (code "43") (name "Net-(D3-Pad1)") (class "Default")
      (node (ref "D3") (pin "1") (pinfunction "1_1") (pintype "unspecified"))
      (node (ref "R1") (pin "2") (pinfunction "2_2") (pintype "unspecified"))
    )
    (net (code "44") (name "Net-(D5-Pad1)") (class "Default")
      (node (ref "D5") (pin "1") (pinfunction "1_1") (pintype "unspecified"))
      (node (ref "R2") (pin "1") (pinfunction "1_1") (pintype "unspecified"))
    )
    (net (code "45") (name "Net-(D7-Pad1)") (class "Default")
      (node (ref "D7") (pin "1") (pinfunction "1_1") (pintype "unspecified"))
      (node (ref "R4") (pin "1") (pinfunction "1_1") (pintype "unspecified"))
    )
    (net (code "46") (name "Net-(D8-Pad1)") (class "Default")
      (node (ref "D8") (pin "1") (pinfunction "1_1") (pintype "unspecified"))
      (node (ref "R5") (pin "1") (pinfunction "1_1") (pintype "unspecified"))
    )
    (net (code "47") (name "Net-(D10-Pad1)") (class "Default")
      (node (ref "D10") (pin "1") (pinfunction "1_1") (pintype "unspecified"))
      (node (ref "R6") (pin "1") (pinfunction "1_1") (pintype "unspecified"))
    )
    (net (code "48") (name "Net-(D12-Pad1)") (class "Default")
      (node (ref "D12") (pin "1") (pinfunction "1_1") (pintype "unspecified"))
      (node (ref "R9") (pin "1") (pinfunction "1_1") (pintype "unspecified"))
    )
    (net (code "49") (name "Net-(D15-Pad1)") (class "Default")
      (node (ref "D15") (pin "1") (pinfunction "1_1") (pintype "unspecified"))
      (node (ref "R18") (pin "1") (pinfunction "1_1") (pintype "unspecified"))
    )
    (net (code "50") (name "Net-(D18-Pad1)") (class "Default")
      (node (ref "D18") (pin "1") (pinfunction "1_1") (pintype "unspecified"))
      (node (ref "R26") (pin "1") (pinfunction "1_1") (pintype "unspecified"))
    )
    (net (code "51") (name "Net-(Q1-B)") (class "Default")
      (node (ref "Q1") (pin "1") (pinfunction "B_1") (pintype "input"))
      (node (ref "R12") (pin "2") (pinfunction "2_2") (pintype "unspecified"))
      (node (ref "R13") (pin "1") (pinfunction "1_1") (pintype "unspecified"))
    )
    (net (code "52") (name "Net-(Q1-C)") (class "Default")
      (node (ref "D10") (pin "2") (pinfunction "2_2") (pintype "unspecified"))
      (node (ref "D9") (pin "1") (pinfunction "1_1") (pintype "unspecified"))
      (node (ref "K1") (pin "2") (pinfunction "2_2") (pintype "input"))
      (node (ref "Q1") (pin "3") (pinfunction "C_3") (pintype "input"))
    )
    (net (code "53") (name "Net-(Q2-B)") (class "Default")
      (node (ref "Q2") (pin "1") (pinfunction "B_1") (pintype "input"))
      (node (ref "R22") (pin "2") (pinfunction "2_2") (pintype "unspecified"))
      (node (ref "R23") (pin "1") (pinfunction "1_1") (pintype "unspecified"))
    )
    (net (code "54") (name "Net-(Q2-C)") (class "Default")
      (node (ref "D14") (pin "1") (pinfunction "1_1") (pintype "unspecified"))
      (node (ref "D15") (pin "2") (pinfunction "2_2") (pintype "unspecified"))
      (node (ref "K2") (pin "2") (pinfunction "2_2") (pintype "input"))
      (node (ref "Q2") (pin "3") (pinfunction "C_3") (pintype "input"))
    )
    (net (code "55") (name "Net-(Q3-B)") (class "Default")
      (node (ref "Q3") (pin "1") (pinfunction "B_1") (pintype "input"))
      (node (ref "R29") (pin "2") (pinfunction "2_2") (pintype "unspecified"))
      (node (ref "R30") (pin "1") (pinfunction "1_1") (pintype "unspecified"))
    )
    (net (code "56") (name "Net-(Q3-C)") (class "Default")
      (node (ref "D17") (pin "1") (pinfunction "1_1") (pintype "unspecified"))
      (node (ref "D18") (pin "2") (pinfunction "2_2") (pintype "unspecified"))
      (node (ref "K3") (pin "2") (pinfunction "2_2") (pintype "input"))
      (node (ref "Q3") (pin "3") (pinfunction "C_3") (pintype "input"))
    )
    (net (code "57") (name "Net-(R7-Pad2)") (class "Default")
      (node (ref "R7") (pin "2") (pinfunction "2_2") (pintype "unspecified"))
      (node (ref "U4") (pin "1") (pinfunction "1_1") (pintype "unspecified"))
    )
    (net (code "58") (name "Net-(R10-Pad2)") (class "Default")
      (node (ref "R10") (pin "2") (pinfunction "2_2") (pintype "unspecified"))
      (node (ref "U6") (pin "1") (pinfunction "1_1") (pintype "unspecified"))
    )
    (net (code "59") (name "Net-(R11-Pad2)") (class "Default")
      (node (ref "R11") (pin "2") (pinfunction "2_2") (pintype "unspecified"))
      (node (ref "U6") (pin "4") (pinfunction "4_4") (pintype "unspecified"))
    )
    (net (code "60") (name "Net-(R12-Pad1)") (class "Default")
      (node (ref "R12") (pin "1") (pinfunction "1_1") (pintype "unspecified"))
      (node (ref "U6") (pin "3") (pinfunction "3_3") (pintype "unspecified"))
    )
    (net (code "61") (name "Net-(R14-Pad2)") (class "Default")
      (node (ref "R14") (pin "2") (pinfunction "2_2") (pintype "unspecified"))
      (node (ref "U7") (pin "1") (pinfunction "1_1") (pintype "unspecified"))
    )
    (net (code "62") (name "Net-(R20-Pad2)") (class "Default")
      (node (ref "R20") (pin "2") (pinfunction "2_2") (pintype "unspecified"))
      (node (ref "U8") (pin "1") (pinfunction "1_1") (pintype "unspecified"))
    )
    (net (code "63") (name "Net-(R21-Pad2)") (class "Default")
      (node (ref "R21") (pin "2") (pinfunction "2_2") (pintype "unspecified"))
      (node (ref "U8") (pin "4") (pinfunction "4_4") (pintype "unspecified"))
    )
    (net (code "64") (name "Net-(R22-Pad1)") (class "Default")
      (node (ref "R22") (pin "1") (pinfunction "1_1") (pintype "unspecified"))
      (node (ref "U8") (pin "3") (pinfunction "3_3") (pintype "unspecified"))
    )
    (net (code "65") (name "Net-(R24-Pad2)") (class "Default")
      (node (ref "R24") (pin "2") (pinfunction "2_2") (pintype "unspecified"))
      (node (ref "U9") (pin "1") (pinfunction "1_1") (pintype "unspecified"))
    )
    (net (code "66") (name "Net-(R27-Pad2)") (class "Default")
      (node (ref "R27") (pin "2") (pinfunction "2_2") (pintype "unspecified"))
      (node (ref "U10") (pin "1") (pinfunction "1_1") (pintype "unspecified"))
    )
    (net (code "67") (name "Net-(R28-Pad2)") (class "Default")
      (node (ref "R28") (pin "2") (pinfunction "2_2") (pintype "unspecified"))
      (node (ref "U10") (pin "4") (pinfunction "4_4") (pintype "unspecified"))
    )
    (net (code "68") (name "Net-(R29-Pad1)") (class "Default")
      (node (ref "R29") (pin "1") (pinfunction "1_1") (pintype "unspecified"))
      (node (ref "U10") (pin "3") (pinfunction "3_3") (pintype "unspecified"))
    )
    (net (code "69") (name "Net-(R31-Pad2)") (class "Default")
      (node (ref "R31") (pin "2") (pinfunction "2_2") (pintype "unspecified"))
      (node (ref "U11") (pin "1") (pinfunction "1_1") (pintype "unspecified"))
    )
    (net (code "70") (name "Net-(R34-Pad2)") (class "Default")
      (node (ref "R34") (pin "2") (pinfunction "2_2") (pintype "unspecified"))
      (node (ref "U12") (pin "1") (pinfunction "1_1") (pintype "unspecified"))
    )
    (net (code "71") (name "Net-(U3-ON{slash}OFF)") (class "Default")
      (node (ref "R3") (pin "1") (pinfunction "1_1") (pintype "unspecified"))
      (node (ref "U3") (pin "4") (pinfunction "ON/OFF_4") (pintype "input"))
    )
    (net (code "72") (name "Net-(U3-OUTPUT)") (class "Default")
      (node (ref "D4") (pin "2") (pinfunction "2_2") (pintype "input"))
      (node (ref "L1") (pin "2") (pinfunction "2_2") (pintype "unspecified"))
      (node (ref "U3") (pin "2") (pinfunction "OUTPUT_2") (pintype "input"))
    )
    (net (code "73") (name "PGND") (class "Default")
      (node (ref "C1") (pin "1") (pinfunction "1_1") (pintype "input"))
      (node (ref "C10") (pin "2") (pinfunction "2_2") (pintype "input"))
      (node (ref "C11") (pin "1") (pinfunction "1_1") (pintype "unspecified"))
      (node (ref "C12") (pin "2") (pintype "unspecified"))
      (node (ref "C7") (pin "2") (pinfunction "2_2") (pintype "input"))
      (node (ref "C8") (pin "1") (pinfunction "1_1") (pintype "unspecified"))
      (node (ref "C9") (pin "1") (pinfunction "1_1") (pintype "input"))
      (node (ref "D11") (pin "1") (pinfunction "K_1") (pintype "input"))
      (node (ref "D11") (pin "2") (pinfunction "K_2") (pintype "input"))
      (node (ref "D13") (pin "1") (pinfunction "K_1") (pintype "input"))
      (node (ref "D13") (pin "2") (pinfunction "K_2") (pintype "input"))
      (node (ref "D16") (pin "1") (pinfunction "K_1") (pintype "input"))
      (node (ref "D16") (pin "2") (pinfunction "K_2") (pintype "input"))
      (node (ref "D5") (pin "2") (pinfunction "2_2") (pintype "unspecified"))
      (node (ref "D6") (pin "1") (pinfunction "1_1") (pintype "input"))
      (node (ref "P1") (pin "1") (pinfunction "1_1") (pintype "input"))
      (node (ref "P2") (pin "2") (pinfunction "2_2") (pintype "input"))
      (node (ref "P3") (pin "1") (pinfunction "1_1") (pintype "input"))
      (node (ref "P4") (pin "2") (pinfunction "2_2") (pintype "input"))
      (node (ref "Q1") (pin "2") (pinfunction "E_2") (pintype "input"))
      (node (ref "Q2") (pin "2") (pinfunction "E_2") (pintype "input"))
      (node (ref "Q3") (pin "2") (pinfunction "E_2") (pintype "input"))
      (node (ref "R13") (pin "2") (pinfunction "2_2") (pintype "unspecified"))
      (node (ref "R23") (pin "2") (pinfunction "2_2") (pintype "unspecified"))
      (node (ref "R3") (pin "2") (pinfunction "2_2") (pintype "unspecified"))
      (node (ref "R30") (pin "2") (pinfunction "2_2") (pintype "unspecified"))
      (node (ref "U1") (pin "2") (pinfunction "GND_2") (pintype "unspecified"))
      (node (ref "U11") (pin "3") (pinfunction "3_3") (pintype "unspecified"))
      (node (ref "U12") (pin "3") (pinfunction "3_3") (pintype "unspecified"))
      (node (ref "U3") (pin "5") (pinfunction "GND_5") (pintype "input"))
      (node (ref "U3") (pin "6") (pinfunction "GND_6") (pintype "input"))
      (node (ref "U3") (pin "7") (pinfunction "GND_7") (pintype "input"))
      (node (ref "U3") (pin "8") (pinfunction "GND_8") (pintype "input"))
    )
    (net (code "74") (name "SGND") (class "Default")
      (node (ref "C13") (pin "2") (pinfunction "2_2") (pintype "unspecified"))
      (node (ref "C14") (pin "2") (pinfunction "2_2") (pintype "unspecified"))
      (node (ref "C15") (pin "1") (pinfunction "1_1") (pintype "unspecified"))
      (node (ref "C16") (pin "1") (pinfunction "1_1") (pintype "unspecified"))
      (node (ref "C17") (pin "1") (pinfunction "1_1") (pintype "unspecified"))
      (node (ref "C18") (pin "1") (pinfunction "1_1") (pintype "unspecified"))
      (node (ref "C2") (pin "1") (pinfunction "1_1") (pintype "input"))
      (node (ref "C3") (pin "1") (pinfunction "1_1") (pintype "input"))
      (node (ref "C4") (pin "1") (pinfunction "1_1") (pintype "input"))
      (node (ref "C5") (pin "1") (pinfunction "1_1") (pintype "input"))
      (node (ref "C6") (pin "1") (pinfunction "1_1") (pintype "unspecified"))
      (node (ref "D2") (pin "1") (pinfunction "1_1") (pintype "input"))
      (node (ref "D3") (pin "2") (pinfunction "2_2") (pintype "unspecified"))
      (node (ref "P9") (pin "1") (pinfunction "1_1") (pintype "input"))
      (node (ref "R16") (pin "1") (pinfunction "1_1") (pintype "unspecified"))
      (node (ref "R17") (pin "1") (pinfunction "1_1") (pintype "unspecified"))
      (node (ref "U1") (pin "4") (pinfunction "0V_4") (pintype "unspecified"))
      (node (ref "U2") (pin "1") (pinfunction "GND_1") (pintype "unspecified"))
      (node (ref "U4") (pin "3") (pinfunction "3_3") (pintype "unspecified"))
      (node (ref "U5") (pin "23") (pinfunction "VSS_1_23") (pintype "unspecified"))
      (node (ref "U5") (pin "35") (pinfunction "VSS_2_35") (pintype "unspecified"))
      (node (ref "U5") (pin "47") (pinfunction "VSS_3_47") (pintype "unspecified"))
      (node (ref "U5") (pin "8") (pinfunction "VSSA_8") (pintype "unspecified"))
      (node (ref "U7") (pin "3") (pinfunction "3_3") (pintype "unspecified"))
      (node (ref "U9") (pin "3") (pinfunction "3_3") (pintype "unspecified"))
    )
    (net (code "75") (name "VIN_24V") (class "Default")
      (node (ref "C7") (pin "1") (pinfunction "1_1") (pintype "input"))
      (node (ref "C8") (pin "2") (pinfunction "2_2") (pintype "unspecified"))
      (node (ref "C9") (pin "2") (pinfunction "2_2") (pintype "input"))
      (node (ref "D1") (pin "2") (pinfunction "2_2") (pintype "unspecified"))
      (node (ref "D14") (pin "2") (pinfunction "2_2") (pintype "unspecified"))
      (node (ref "D17") (pin "2") (pinfunction "2_2") (pintype "unspecified"))
      (node (ref "D9") (pin "2") (pinfunction "2_2") (pintype "unspecified"))
      (node (ref "K1") (pin "1") (pinfunction "1_1") (pintype "input"))
      (node (ref "K2") (pin "1") (pinfunction "1_1") (pintype "input"))
      (node (ref "K3") (pin "1") (pinfunction "1_1") (pintype "input"))
      (node (ref "R11") (pin "1") (pinfunction "1_1") (pintype "unspecified"))
      (node (ref "R14") (pin "1") (pinfunction "1_1") (pintype "unspecified"))
      (node (ref "R18") (pin "2") (pinfunction "2_2") (pintype "unspecified"))
      (node (ref "R2") (pin "2") (pinfunction "2_2") (pintype "unspecified"))
      (node (ref "R21") (pin "1") (pinfunction "1_1") (pintype "unspecified"))
      (node (ref "R24") (pin "1") (pinfunction "1_1") (pintype "unspecified"))
      (node (ref "R26") (pin "2") (pinfunction "2_2") (pintype "unspecified"))
      (node (ref "R28") (pin "1") (pinfunction "1_1") (pintype "unspecified"))
      (node (ref "R32") (pin "1") (pinfunction "1_1") (pintype "unspecified"))
      (node (ref "R35") (pin "1") (pinfunction "1_1") (pintype "unspecified"))
      (node (ref "R6") (pin "2") (pinfunction "2_2") (pintype "unspecified"))
      (node (ref "R7") (pin "1") (pinfunction "1_1") (pintype "unspecified"))
      (node (ref "U3") (pin "1") (pinfunction "VIN_1") (pintype "input"))
    )
    (net (code "76") (name "unconnected-(U5-PA15{slash}JTDI-Pad38)") (class "Default")
      (node (ref "U5") (pin "38") (pinfunction "PA15/JTDI_38") (pintype "bidirectional"))
    )
    (net (code "77") (name "unconnected-(U5-PB0-Pad18)") (class "Default")
      (node (ref "U5") (pin "18") (pinfunction "PB0_18") (pintype "bidirectional"))
    )
    (net (code "78") (name "unconnected-(U5-PB1-Pad19)") (class "Default")
      (node (ref "U5") (pin "19") (pinfunction "PB1_19") (pintype "bidirectional"))
    )
    (net (code "79") (name "unconnected-(U5-PB3{slash}JTDO-Pad39)") (class "Default")
      (node (ref "U5") (pin "39") (pinfunction "PB3/JTDO_39") (pintype "bidirectional"))
    )
    (net (code "80") (name "unconnected-(U5-PB4{slash}JNTRST-Pad40)") (class "Default")
      (node (ref "U5") (pin "40") (pinfunction "PB4/JNTRST_40") (pintype "bidirectional"))
    )
    (net (code "81") (name "unconnected-(U5-PB5-Pad41)") (class "Default")
      (node (ref "U5") (pin "41") (pinfunction "PB5_41") (pintype "bidirectional"))
    )
    (net (code "82") (name "unconnected-(U5-PB6-Pad42)") (class "Default")
      (node (ref "U5") (pin "42") (pinfunction "PB6_42") (pintype "bidirectional"))
    )
    (net (code "83") (name "unconnected-(U5-PB7-Pad43)") (class "Default")
      (node (ref "U5") (pin "43") (pinfunction "PB7_43") (pintype "bidirectional"))
    )
    (net (code "84") (name "unconnected-(U5-PB8-Pad45)") (class "Default")
      (node (ref "U5") (pin "45") (pinfunction "PB8_45") (pintype "bidirectional"))
    )
    (net (code "85") (name "unconnected-(U5-PB10-Pad21)") (class "Default")
      (node (ref "U5") (pin "21") (pinfunction "PB10_21") (pintype "bidirectional"))
    )
    (net (code "86") (name "unconnected-(U5-PB11-Pad22)") (class "Default")
      (node (ref "U5") (pin "22") (pinfunction "PB11_22") (pintype "bidirectional"))
    )
    (net (code "87") (name "unconnected-(U5-PC13-TAMPER-RTC-Pad2)") (class "Default")
      (node (ref "U5") (pin "2") (pinfunction "PC13-TAMPER-RTC_2") (pintype "bidirectional"))
    )
    (net (code "88") (name "unconnected-(U5-PC14-OSC32_IN-Pad3)") (class "Default")
      (node (ref "U5") (pin "3") (pinfunction "PC14-OSC32_IN_3") (pintype "bidirectional"))
    )
    (net (code "89") (name "unconnected-(U5-PC15-OSC32_OUT-Pad4)") (class "Default")
      (node (ref "U5") (pin "4") (pinfunction "PC15-OSC32_OUT_4") (pintype "bidirectional"))
    )
    (net (code "90") (name "unconnected-(U5-VBAT-Pad1)") (class "Default")
      (node (ref "U5") (pin "1") (pinfunction "VBAT_1") (pintype "unspecified"))
    )
  )
)
